# bird_beaks.net
KiCad netlist of a schematic drawn in EAGLE
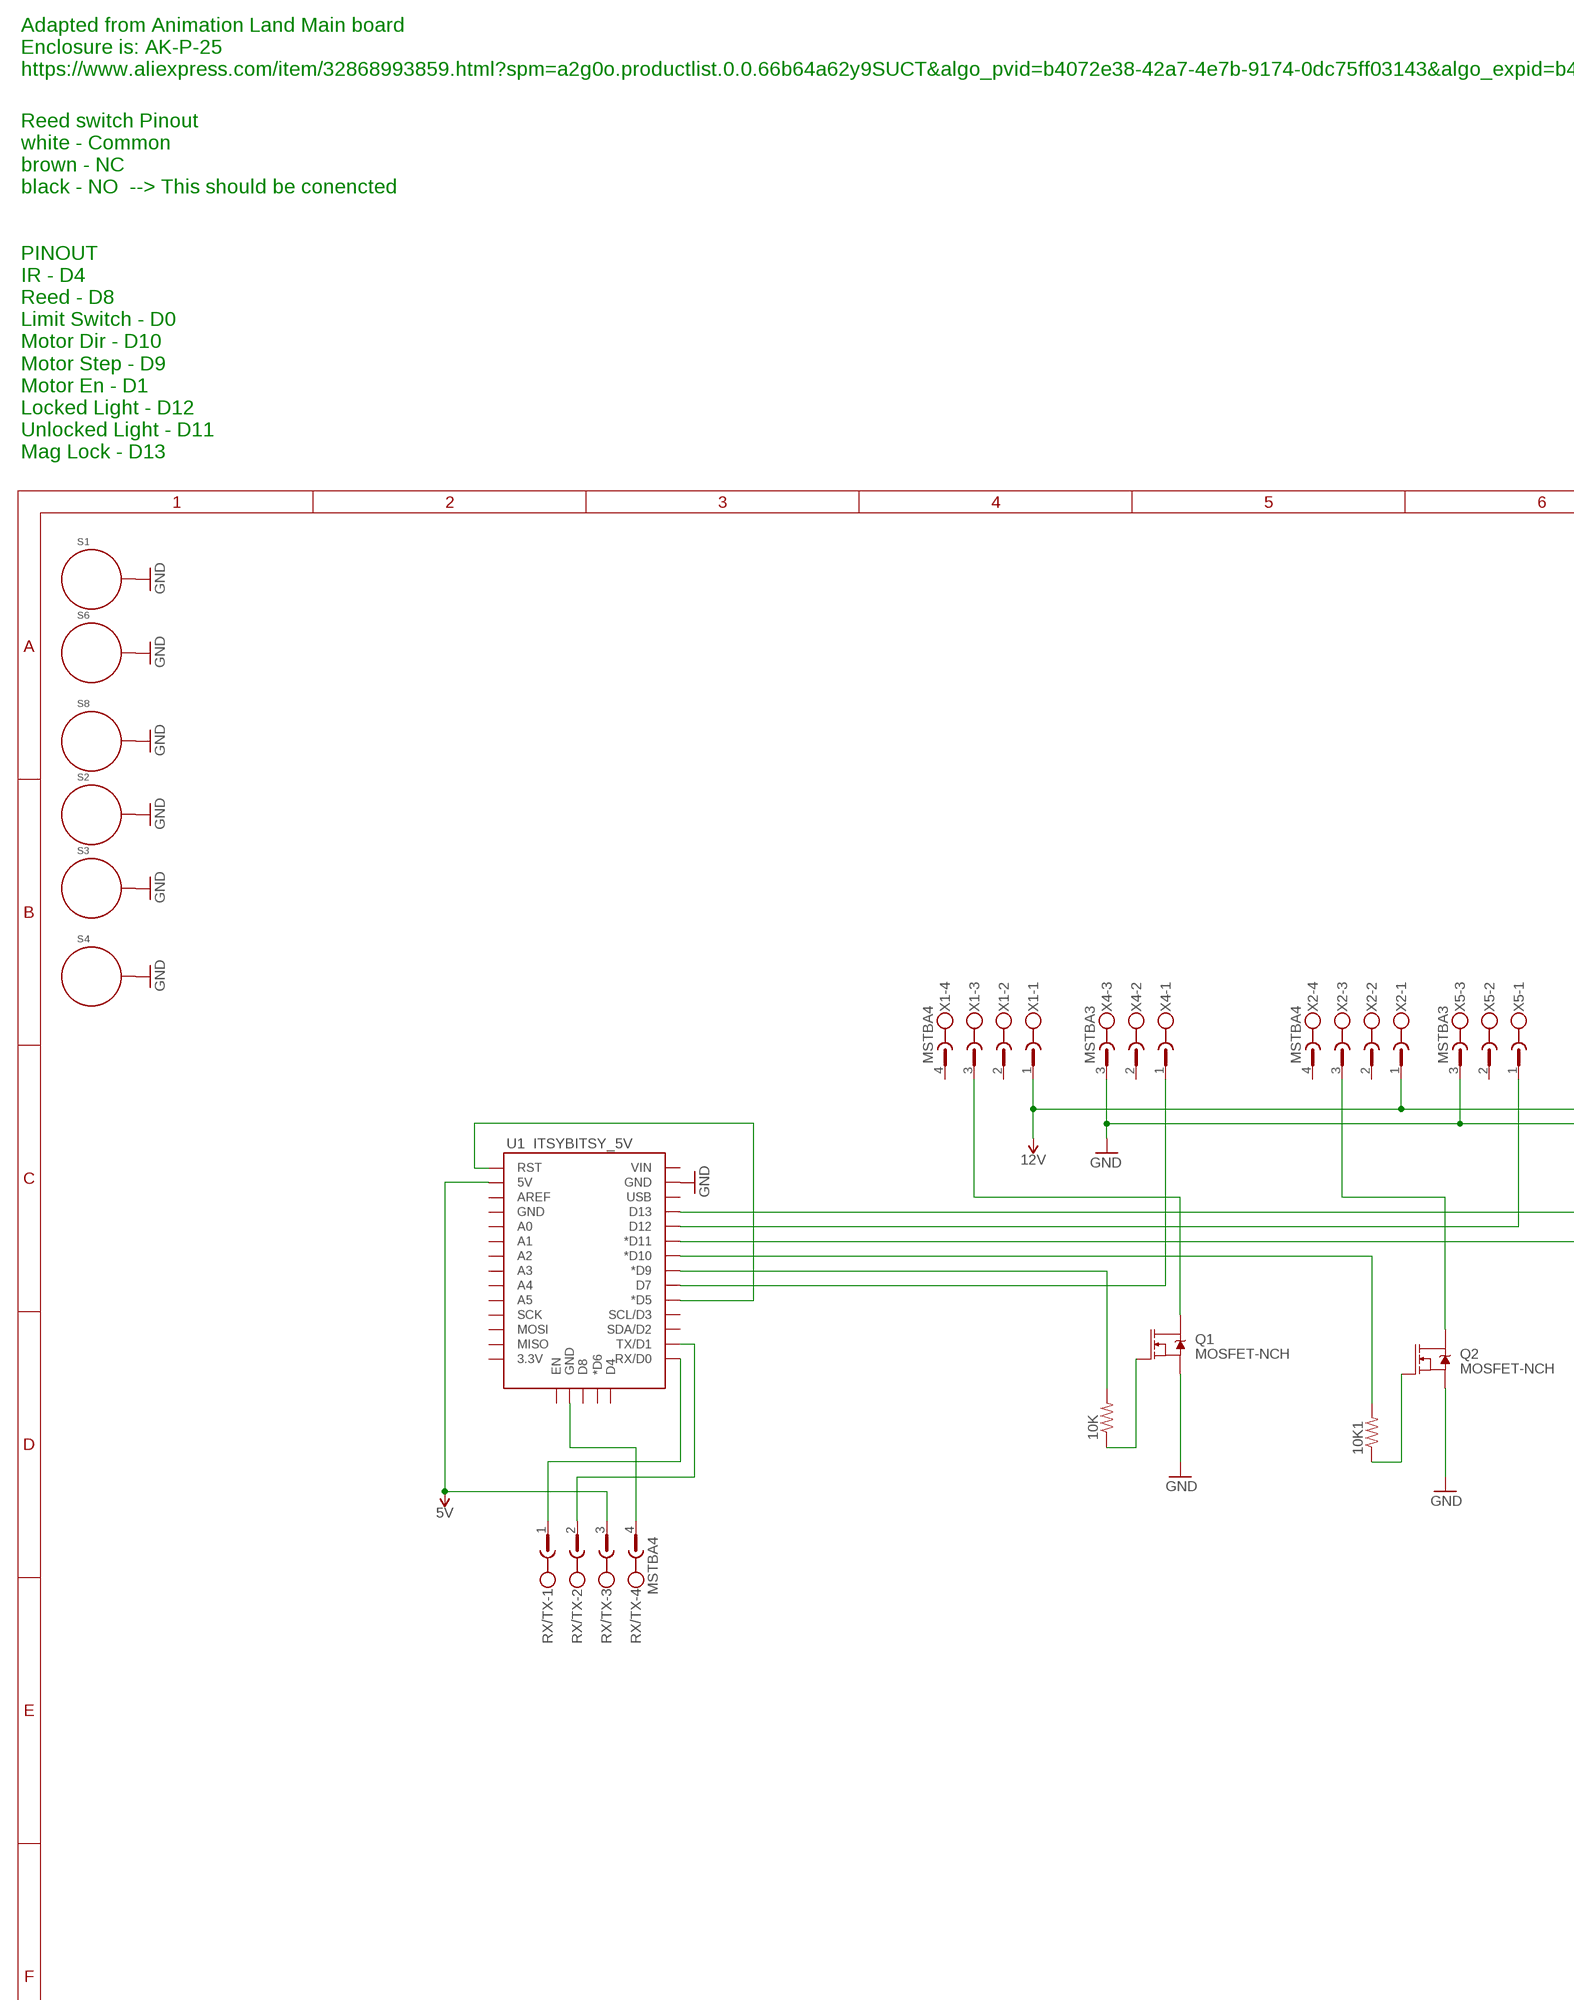
[diagram p0: schematic, sheet 1, part 1 of 2]
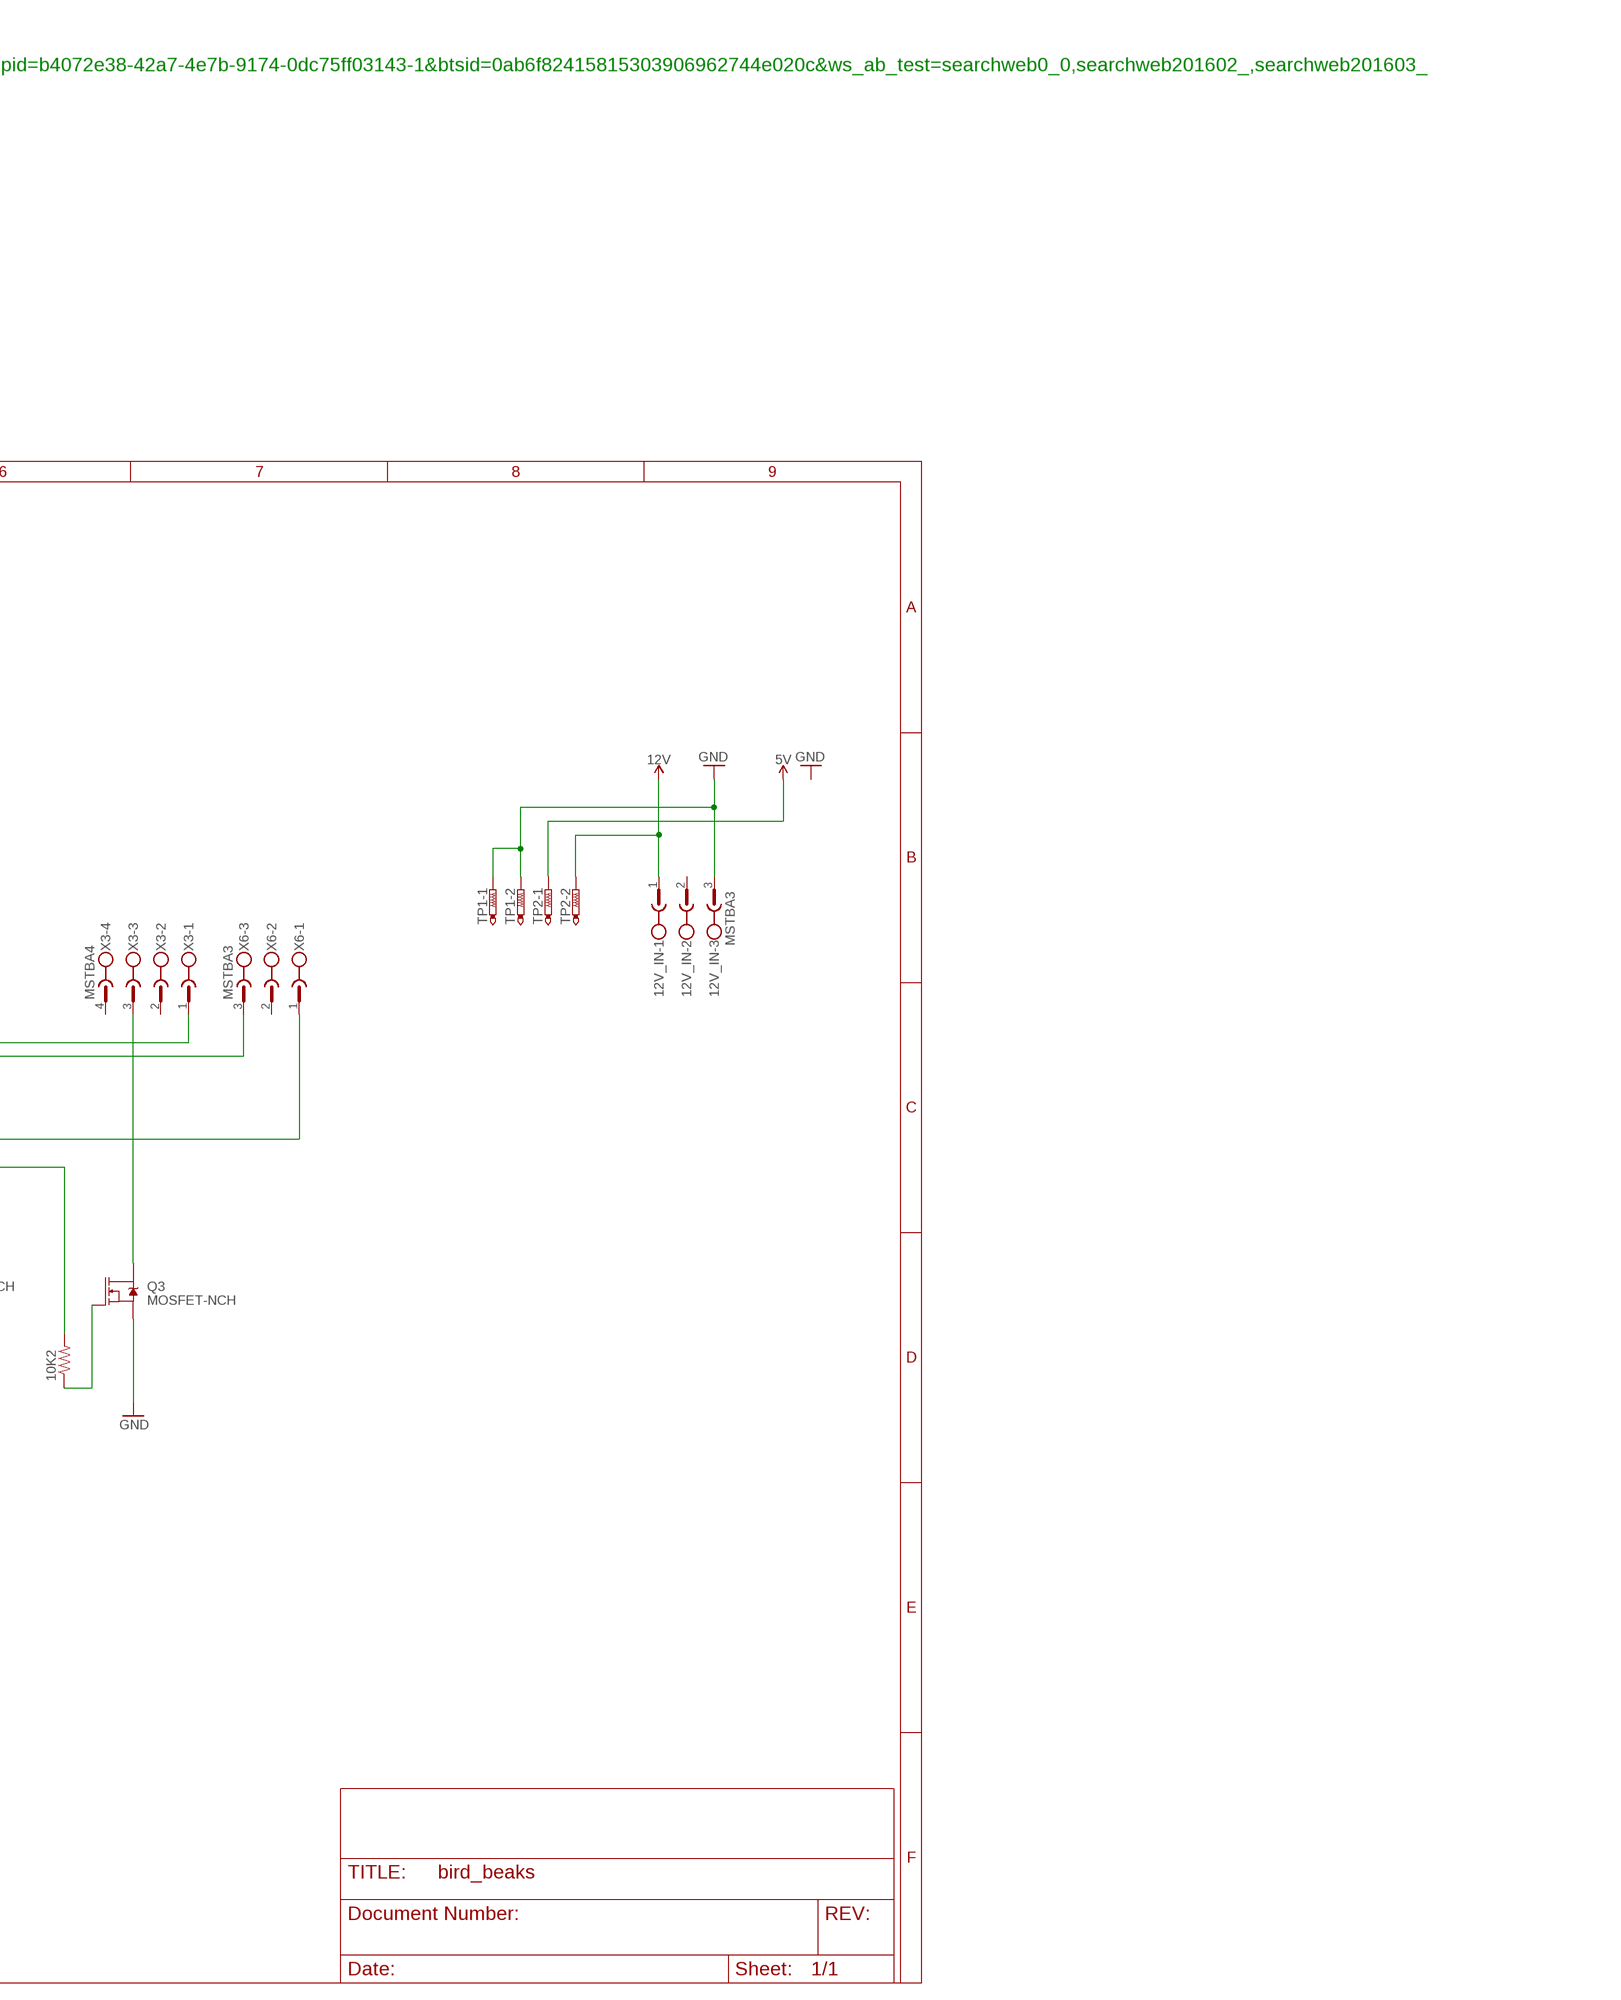
[diagram p1: schematic, sheet 1, part 2 of 2]

(export (version "E")
  (design (tool "Eeschema 10.0.6"))
  (components
    (comp (ref "10K")
      (value "R-US_M0805")
      (footprint "eagle-import:M0805")
      (libsource (lib "eagle-import") (part "R-US_M0805"))
    )
    (comp (ref "10K1")
      (value "R-US_M0805")
      (footprint "eagle-import:M0805")
      (libsource (lib "eagle-import") (part "R-US_M0805"))
    )
    (comp (ref "10K2")
      (value "R-US_M0805")
      (footprint "eagle-import:M0805")
      (libsource (lib "eagle-import") (part "R-US_M0805"))
    )
    (comp (ref "12V_IN")
      (value "MSTBA3")
      (footprint "eagle-import:MSTBA3")
      (fields (field (name "MF") "FARNELL") (field (name "MPN") "1757255"))
      (libsource (lib "eagle-import") (part "MSTBA3"))
    )
    (comp (ref "Q1")
      (value "MOSFET-NCH")
      (footprint "eagle-import:SO-8_POWER_PAK")
      (libsource (lib "eagle-import") (part "MOSFET-NCH"))
    )
    (comp (ref "Q2")
      (value "MOSFET-NCH")
      (footprint "eagle-import:SO-8_POWER_PAK")
      (libsource (lib "eagle-import") (part "MOSFET-NCH"))
    )
    (comp (ref "Q3")
      (value "MOSFET-NCH")
      (footprint "eagle-import:SO-8_POWER_PAK")
      (libsource (lib "eagle-import") (part "MOSFET-NCH"))
    )
    (comp (ref "RX/TX")
      (value "MSTBA4")
      (footprint "eagle-import:MSTBA4")
      (fields (field (name "MF") "FARNELL") (field (name "MPN") "1757268"))
      (libsource (lib "eagle-import") (part "th_libraries_26281734_MSTBA4"))
    )
    (comp (ref "S1")
      (value "STANDOFF_ELECTRICAL5-32")
      (footprint "eagle-import:STANDOFF_ELECTRICAL_5_32")
      (libsource (lib "eagle-import") (part "STANDOFF_ELECTRICAL5-32"))
    )
    (comp (ref "S2")
      (value "STANDOFF_ELECTRICAL5-32")
      (footprint "eagle-import:STANDOFF_ELECTRICAL_5_32")
      (libsource (lib "eagle-import") (part "STANDOFF_ELECTRICAL5-32"))
    )
    (comp (ref "S3")
      (value "STANDOFF_ELECTRICAL5-32")
      (footprint "eagle-import:STANDOFF_ELECTRICAL_5_32")
      (libsource (lib "eagle-import") (part "STANDOFF_ELECTRICAL5-32"))
    )
    (comp (ref "S4")
      (value "STANDOFF_ELECTRICAL5-32")
      (footprint "eagle-import:STANDOFF_ELECTRICAL_5_32")
      (libsource (lib "eagle-import") (part "STANDOFF_ELECTRICAL5-32"))
    )
    (comp (ref "S6")
      (value "STANDOFF_ELECTRICAL5-32")
      (footprint "eagle-import:STANDOFF_ELECTRICAL_5_32")
      (libsource (lib "eagle-import") (part "STANDOFF_ELECTRICAL5-32"))
    )
    (comp (ref "S8")
      (value "STANDOFF_ELECTRICAL5-32")
      (footprint "eagle-import:STANDOFF_ELECTRICAL_5_32")
      (libsource (lib "eagle-import") (part "STANDOFF_ELECTRICAL5-32"))
    )
    (comp (ref "TP1")
      (value "PTR2")
      (footprint "eagle-import:P2-38-17")
      (libsource (lib "eagle-import") (part "PTR2"))
    )
    (comp (ref "TP2")
      (value "PTR2")
      (footprint "eagle-import:P2-38-17")
      (libsource (lib "eagle-import") (part "PTR2"))
    )
    (comp (ref "U1")
      (value "ITSYBITSY_5V")
      (footprint "eagle-import:ADAFRUIT_LENOARDO")
      (libsource (lib "eagle-import") (part "ITSYBITSY_5V"))
    )
    (comp (ref "X1")
      (value "MSTBA4")
      (footprint "eagle-import:MSTBA4")
      (fields (field (name "MF") "FARNELL") (field (name "MPN") "1757268"))
      (libsource (lib "eagle-import") (part "MSTBA4"))
    )
    (comp (ref "X2")
      (value "MSTBA4")
      (footprint "eagle-import:MSTBA4")
      (fields (field (name "MF") "FARNELL") (field (name "MPN") "1757268"))
      (libsource (lib "eagle-import") (part "MSTBA4"))
    )
    (comp (ref "X3")
      (value "MSTBA4")
      (footprint "eagle-import:MSTBA4")
      (fields (field (name "MF") "FARNELL") (field (name "MPN") "1757268"))
      (libsource (lib "eagle-import") (part "MSTBA4"))
    )
    (comp (ref "X4")
      (value "MSTBA3")
      (footprint "eagle-import:MSTBA3")
      (fields (field (name "MF") "FARNELL") (field (name "MPN") "1757255"))
      (libsource (lib "eagle-import") (part "MSTBA3"))
    )
    (comp (ref "X5")
      (value "MSTBA3")
      (footprint "eagle-import:MSTBA3")
      (fields (field (name "MF") "FARNELL") (field (name "MPN") "1757255"))
      (libsource (lib "eagle-import") (part "MSTBA3"))
    )
    (comp (ref "X6")
      (value "MSTBA3")
      (footprint "eagle-import:MSTBA3")
      (fields (field (name "MF") "FARNELL") (field (name "MPN") "1757255"))
      (libsource (lib "eagle-import") (part "MSTBA3"))
    )
  )
  (nets
    (net (code "1") (name "5V") (class "Default")
      (node (ref "RX/TX") (pin "3") (pinfunction "1_3") (pintype "passive"))
      (node (ref "TP2") (pin "TP-1") (pinfunction "TP_TP-1") (pintype "input"))
      (node (ref "U1") (pin "5V") (pinfunction "5V_5V") (pintype "bidirectional"))
    )
    (net (code "2") (name "12V") (class "Default")
      (node (ref "12V_IN") (pin "1") (pinfunction "1_1") (pintype "passive"))
      (node (ref "TP2") (pin "TP-2") (pinfunction "TP_TP-2") (pintype "input"))
      (node (ref "X1") (pin "1") (pinfunction "1_1") (pintype "passive"))
      (node (ref "X2") (pin "1") (pinfunction "1_1") (pintype "passive"))
      (node (ref "X3") (pin "1") (pinfunction "1_1") (pintype "passive"))
    )
    (net (code "3") (name "GND") (class "Default")
      (node (ref "12V_IN") (pin "3") (pinfunction "1_3") (pintype "passive"))
      (node (ref "Q1") (pin "S") (pinfunction "S_S") (pintype "bidirectional"))
      (node (ref "Q2") (pin "S") (pinfunction "S_S") (pintype "bidirectional"))
      (node (ref "Q3") (pin "S") (pinfunction "S_S") (pintype "bidirectional"))
      (node (ref "S1") (pin "P1") (pinfunction "P$1_P1") (pintype "bidirectional"))
      (node (ref "S2") (pin "P1") (pinfunction "P$1_P1") (pintype "bidirectional"))
      (node (ref "S3") (pin "P1") (pinfunction "P$1_P1") (pintype "bidirectional"))
      (node (ref "S4") (pin "P1") (pinfunction "P$1_P1") (pintype "bidirectional"))
      (node (ref "S6") (pin "P1") (pinfunction "P$1_P1") (pintype "bidirectional"))
      (node (ref "S8") (pin "P1") (pinfunction "P$1_P1") (pintype "bidirectional"))
      (node (ref "TP1") (pin "TP-1") (pinfunction "TP_TP-1") (pintype "input"))
      (node (ref "TP1") (pin "TP-2") (pinfunction "TP_TP-2") (pintype "input"))
      (node (ref "U1") (pin "GND@2") (pinfunction "GND_GND@2") (pintype "bidirectional"))
      (node (ref "X4") (pin "3") (pinfunction "1_3") (pintype "passive"))
      (node (ref "X5") (pin "3") (pinfunction "1_3") (pintype "passive"))
      (node (ref "X6") (pin "3") (pinfunction "1_3") (pintype "passive"))
    )
    (net (code "4") (name "Net-(10K-Pad1)") (class "Default")
      (node (ref "10K") (pin "1") (pinfunction "1_1") (pintype "passive"))
      (node (ref "Q1") (pin "G") (pinfunction "G_G") (pintype "bidirectional"))
    )
    (net (code "5") (name "Net-(10K1-Pad1)") (class "Default")
      (node (ref "10K1") (pin "1") (pinfunction "1_1") (pintype "passive"))
      (node (ref "Q2") (pin "G") (pinfunction "G_G") (pintype "bidirectional"))
    )
    (net (code "6") (name "Net-(10K2-Pad1)") (class "Default")
      (node (ref "10K2") (pin "1") (pinfunction "1_1") (pintype "passive"))
      (node (ref "Q3") (pin "G") (pinfunction "G_G") (pintype "bidirectional"))
    )
    (net (code "7") (name "Net-(Q1-D)") (class "Default")
      (node (ref "Q1") (pin "D1") (pinfunction "D_D1") (pintype "bidirectional"))
      (node (ref "X1") (pin "3") (pinfunction "1_3") (pintype "passive"))
    )
    (net (code "8") (name "Net-(Q2-D)") (class "Default")
      (node (ref "Q2") (pin "D1") (pinfunction "D_D1") (pintype "bidirectional"))
      (node (ref "X2") (pin "3") (pinfunction "1_3") (pintype "passive"))
    )
    (net (code "9") (name "Net-(Q3-D)") (class "Default")
      (node (ref "Q3") (pin "D1") (pinfunction "D_D1") (pintype "bidirectional"))
      (node (ref "X3") (pin "3") (pinfunction "1_3") (pintype "passive"))
    )
    (net (code "10") (name "Net-(RX/TXB-1)") (class "Default")
      (node (ref "RX/TX") (pin "2") (pinfunction "1_2") (pintype "passive"))
      (node (ref "U1") (pin "TX") (pinfunction "TX/D1_TX") (pintype "bidirectional"))
    )
    (net (code "11") (name "Net-(RX/TXD-1)") (class "Default")
      (node (ref "RX/TX") (pin "4") (pinfunction "1_4") (pintype "passive"))
      (node (ref "U1") (pin "GND@1") (pinfunction "GND_GND@1") (pintype "bidirectional"))
    )
    (net (code "12") (name "Net-(U1-*D5)") (class "Default")
      (node (ref "U1") (pin "D5") (pinfunction "*D5_D5") (pintype "bidirectional"))
      (node (ref "U1") (pin "RES") (pinfunction "RST_RES") (pintype "bidirectional"))
    )
    (net (code "13") (name "Net-(U1-*D9)") (class "Default")
      (node (ref "10K") (pin "2") (pinfunction "2_2") (pintype "passive"))
      (node (ref "U1") (pin "D9") (pinfunction "*D9_D9") (pintype "bidirectional"))
    )
    (net (code "14") (name "Net-(U1-*D10)") (class "Default")
      (node (ref "10K1") (pin "2") (pinfunction "2_2") (pintype "passive"))
      (node (ref "U1") (pin "D10") (pinfunction "*D10_D10") (pintype "bidirectional"))
    )
    (net (code "15") (name "Net-(U1-*D11)") (class "Default")
      (node (ref "10K2") (pin "2") (pinfunction "2_2") (pintype "passive"))
      (node (ref "U1") (pin "D11") (pinfunction "*D11_D11") (pintype "bidirectional"))
    )
    (net (code "16") (name "Net-(U1-PadD7)") (class "Default")
      (node (ref "U1") (pin "D7") (pinfunction "D7_D7") (pintype "bidirectional"))
      (node (ref "X4") (pin "1") (pinfunction "1_1") (pintype "passive"))
    )
    (net (code "17") (name "Net-(U1-PadD12)") (class "Default")
      (node (ref "U1") (pin "D12") (pinfunction "D12_D12") (pintype "bidirectional"))
      (node (ref "X5") (pin "1") (pinfunction "1_1") (pintype "passive"))
    )
    (net (code "18") (name "Net-(U1-PadD13)") (class "Default")
      (node (ref "U1") (pin "D13") (pinfunction "D13_D13") (pintype "bidirectional"))
      (node (ref "X6") (pin "1") (pinfunction "1_1") (pintype "passive"))
    )
    (net (code "19") (name "Net-(U1-RX{slash}D0)") (class "Default")
      (node (ref "RX/TX") (pin "1") (pinfunction "1_1") (pintype "passive"))
      (node (ref "U1") (pin "RX") (pinfunction "RX/D0_RX") (pintype "bidirectional"))
    )
    (net (code "20") (name "unconnected-(12V_INB-1-Pad2)") (class "Default")
      (node (ref "12V_IN") (pin "2") (pinfunction "1_2") (pintype "passive"))
    )
    (net (code "21") (name "unconnected-(U1-*D6-PadD6)") (class "Default")
      (node (ref "U1") (pin "D6") (pinfunction "*D6_D6") (pintype "bidirectional"))
    )
    (net (code "22") (name "unconnected-(U1-3.3V-Pad3V)") (class "Default")
      (node (ref "U1") (pin "3V") (pinfunction "3.3V_3V") (pintype "bidirectional"))
    )
    (net (code "23") (name "unconnected-(U1-GND-PadGND@0)") (class "Default")
      (node (ref "U1") (pin "GND@0") (pinfunction "GND_GND@0") (pintype "bidirectional"))
    )
    (net (code "24") (name "unconnected-(U1-PadA0)") (class "Default")
      (node (ref "U1") (pin "A0") (pinfunction "A0_A0") (pintype "bidirectional"))
    )
    (net (code "25") (name "unconnected-(U1-PadA1)") (class "Default")
      (node (ref "U1") (pin "A1") (pinfunction "A1_A1") (pintype "bidirectional"))
    )
    (net (code "26") (name "unconnected-(U1-PadA2)") (class "Default")
      (node (ref "U1") (pin "A2") (pinfunction "A2_A2") (pintype "bidirectional"))
    )
    (net (code "27") (name "unconnected-(U1-PadA3)") (class "Default")
      (node (ref "U1") (pin "A3") (pinfunction "A3_A3") (pintype "bidirectional"))
    )
    (net (code "28") (name "unconnected-(U1-PadA4)") (class "Default")
      (node (ref "U1") (pin "A4") (pinfunction "A4_A4") (pintype "bidirectional"))
    )
    (net (code "29") (name "unconnected-(U1-PadA5)") (class "Default")
      (node (ref "U1") (pin "A5") (pinfunction "A5_A5") (pintype "bidirectional"))
    )
    (net (code "30") (name "unconnected-(U1-PadAREF)") (class "Default")
      (node (ref "U1") (pin "AREF") (pinfunction "AREF_AREF") (pintype "bidirectional"))
    )
    (net (code "31") (name "unconnected-(U1-PadD4)") (class "Default")
      (node (ref "U1") (pin "D4") (pinfunction "D4_D4") (pintype "bidirectional"))
    )
    (net (code "32") (name "unconnected-(U1-PadD8)") (class "Default")
      (node (ref "U1") (pin "D8") (pinfunction "D8_D8") (pintype "bidirectional"))
    )
    (net (code "33") (name "unconnected-(U1-PadEN)") (class "Default")
      (node (ref "U1") (pin "EN") (pinfunction "EN_EN") (pintype "bidirectional"))
    )
    (net (code "34") (name "unconnected-(U1-PadMISO)") (class "Default")
      (node (ref "U1") (pin "MISO") (pinfunction "MISO_MISO") (pintype "bidirectional"))
    )
    (net (code "35") (name "unconnected-(U1-PadMOSI)") (class "Default")
      (node (ref "U1") (pin "MOSI") (pinfunction "MOSI_MOSI") (pintype "bidirectional"))
    )
    (net (code "36") (name "unconnected-(U1-PadSCK)") (class "Default")
      (node (ref "U1") (pin "SCK") (pinfunction "SCK_SCK") (pintype "bidirectional"))
    )
    (net (code "37") (name "unconnected-(U1-PadUSB)") (class "Default")
      (node (ref "U1") (pin "USB") (pinfunction "USB_USB") (pintype "bidirectional"))
    )
    (net (code "38") (name "unconnected-(U1-PadVIN)") (class "Default")
      (node (ref "U1") (pin "VIN") (pinfunction "VIN_VIN") (pintype "bidirectional"))
    )
    (net (code "39") (name "unconnected-(U1-SCL{slash}D3-PadSCL)") (class "Default")
      (node (ref "U1") (pin "SCL") (pinfunction "SCL/D3_SCL") (pintype "bidirectional"))
    )
    (net (code "40") (name "unconnected-(U1-SDA{slash}D2-PadSDA)") (class "Default")
      (node (ref "U1") (pin "SDA") (pinfunction "SDA/D2_SDA") (pintype "bidirectional"))
    )
    (net (code "41") (name "unconnected-(X1B-1-Pad2)") (class "Default")
      (node (ref "X1") (pin "2") (pinfunction "1_2") (pintype "passive"))
    )
    (net (code "42") (name "unconnected-(X1D-1-Pad4)") (class "Default")
      (node (ref "X1") (pin "4") (pinfunction "1_4") (pintype "passive"))
    )
    (net (code "43") (name "unconnected-(X2B-1-Pad2)") (class "Default")
      (node (ref "X2") (pin "2") (pinfunction "1_2") (pintype "passive"))
    )
    (net (code "44") (name "unconnected-(X2D-1-Pad4)") (class "Default")
      (node (ref "X2") (pin "4") (pinfunction "1_4") (pintype "passive"))
    )
    (net (code "45") (name "unconnected-(X3B-1-Pad2)") (class "Default")
      (node (ref "X3") (pin "2") (pinfunction "1_2") (pintype "passive"))
    )
    (net (code "46") (name "unconnected-(X3D-1-Pad4)") (class "Default")
      (node (ref "X3") (pin "4") (pinfunction "1_4") (pintype "passive"))
    )
    (net (code "47") (name "unconnected-(X4B-1-Pad2)") (class "Default")
      (node (ref "X4") (pin "2") (pinfunction "1_2") (pintype "passive"))
    )
    (net (code "48") (name "unconnected-(X5B-1-Pad2)") (class "Default")
      (node (ref "X5") (pin "2") (pinfunction "1_2") (pintype "passive"))
    )
    (net (code "49") (name "unconnected-(X6B-1-Pad2)") (class "Default")
      (node (ref "X6") (pin "2") (pinfunction "1_2") (pintype "passive"))
    )
  )
)
